# Speisung.net
KiCad netlist of a schematic drawn in Altium Designer
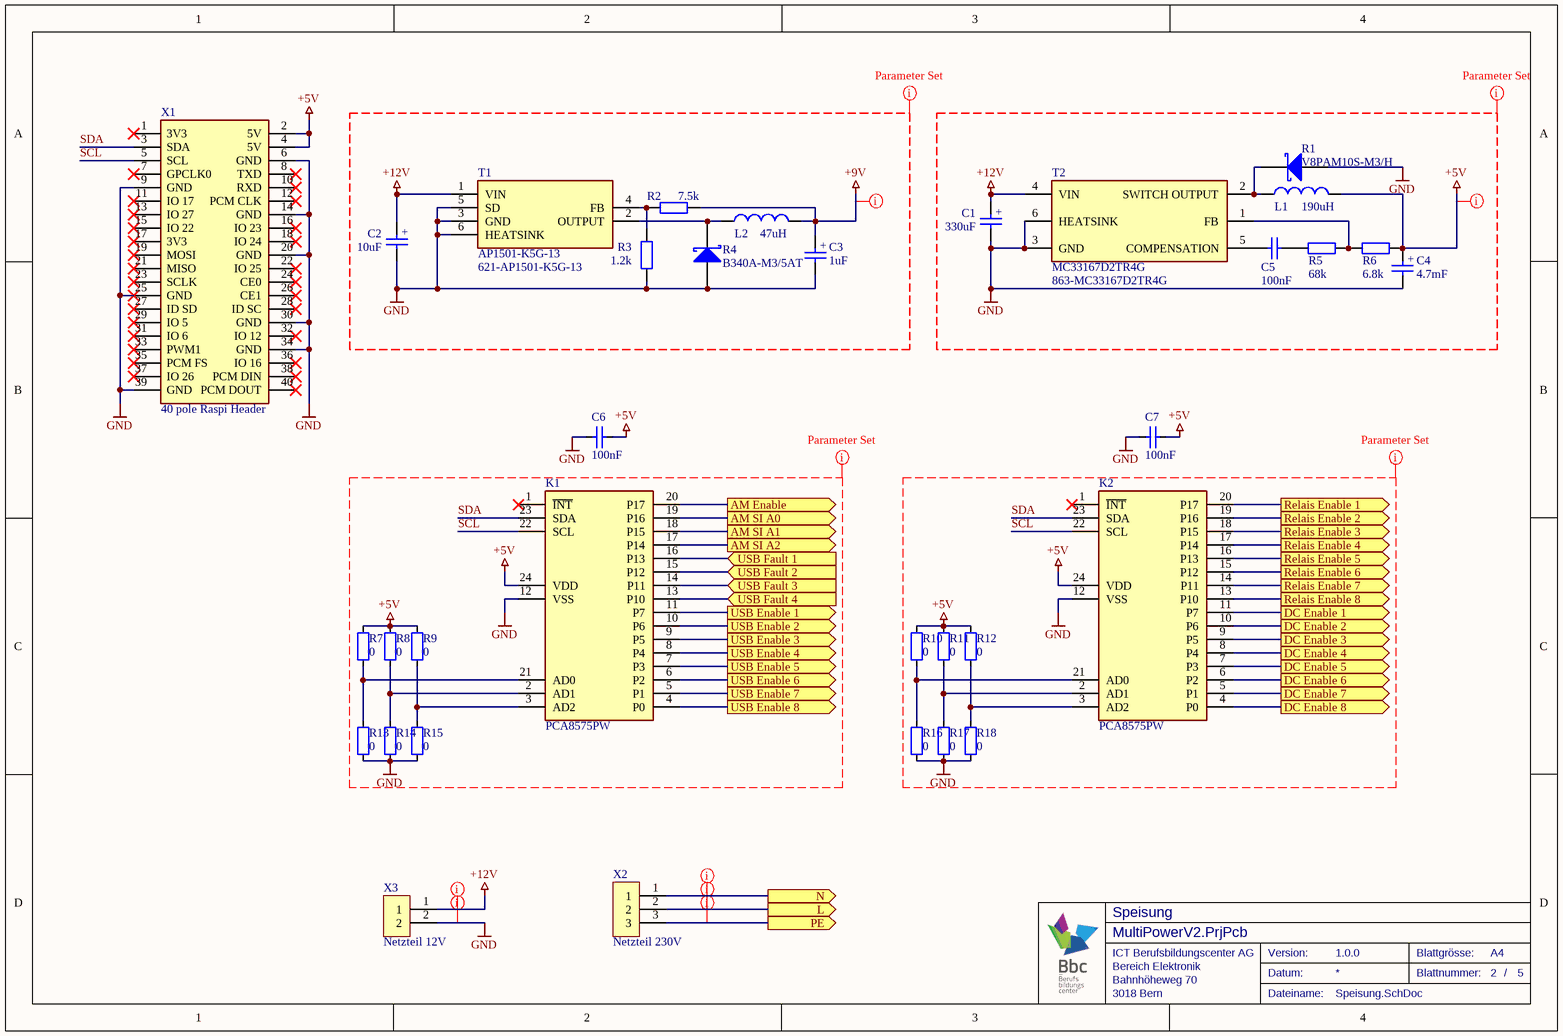
[diagram p0: Speisung.SchDoc]

(export (version "E")
  (design (tool "Eeschema 10.0.6"))
  (components
    (comp (ref "C1")
      (value "330uF")
      (footprint "T521X337M016ATE015")
      (description "Polarized Capacitor")
      (fields (field (name "Comment") "Capacitor") (field (name "PUBLISHER") "ICT Berufsbildungscenter AG"))
      (libsource (lib "BBC_Components") (part "Capacitor P"))
    )
    (comp (ref "C2")
      (value "10uF")
      (footprint "CAP TAN A R")
      (description "Polarized Capacitor")
      (fields (field (name "Comment") "Capacitor") (field (name "PUBLISHER") "ICT Berufsbildungscenter AG"))
      (libsource (lib "BBC_Components") (part "Capacitor P"))
    )
    (comp (ref "C3")
      (value "1uF")
      (footprint "R82EC4100Z370J")
      (description "Polarized Capacitor")
      (fields (field (name "Comment") "Capacitor") (field (name "PUBLISHER") "ICT Berufsbildungscenter AG"))
      (libsource (lib "BBC_Components") (part "Capacitor P"))
    )
    (comp (ref "C4")
      (value "4.7mF")
      (footprint "CAP ELKO 12.5x20x5 S")
      (description "Polarized Capacitor")
      (fields (field (name "Comment") "Capacitor") (field (name "PUBLISHER") "ICT Berufsbildungscenter AG"))
      (libsource (lib "BBC_Components") (part "Capacitor P"))
    )
    (comp (ref "C5")
      (value "100nF")
      (footprint "CAP CER 1206 H")
      (description "Non polarized capacitor")
      (fields (field (name "Comment") "Capacitor") (field (name "PUBLISHER") "ICT Berufsbildungscenter AG"))
      (libsource (lib "BBC_Components") (part "Capacitor"))
    )
    (comp (ref "C6")
      (value "100nF")
      (footprint "CAP CER 0805 R")
      (description "Non polarized capacitor")
      (fields (field (name "Comment") "Capacitor") (field (name "PUBLISHER") "ICT Berufsbildungscenter AG"))
      (libsource (lib "SchematicLibrary") (part "Capacitor"))
    )
    (comp (ref "C7")
      (value "100nF")
      (footprint "CAP CER 0805 R")
      (description "Non polarized capacitor")
      (fields (field (name "Comment") "Capacitor") (field (name "PUBLISHER") "ICT Berufsbildungscenter AG"))
      (libsource (lib "SchematicLibrary") (part "Capacitor"))
    )
    (comp (ref "K1")
      (value "PCA8575PW")
      (footprint "TSOP65P640X110-24M")
      (libsource (lib "SchematicLibrary") (part "PCA8575PW"))
    )
    (comp (ref "K2")
      (value "PCA8575PW")
      (footprint "TSOP65P640X110-24M")
      (libsource (lib "SchematicLibrary") (part "PCA8575PW"))
    )
    (comp (ref "L1")
      (value "190uH")
      (footprint "SHBC14-1R2A0187V")
      (description "Inductor")
      (fields (field (name "PUBLISHER") "ICT Berufsbildungscenter AG"))
      (libsource (lib "BBC_Components") (part "Inductor"))
    )
    (comp (ref "L2")
      (value "47uH")
      (footprint "SRP1038C6R8M")
      (description "Inductor")
      (fields (field (name "PUBLISHER") "ICT Berufsbildungscenter AG"))
      (libsource (lib "BBC_Components") (part "Inductor"))
    )
    (comp (ref "R1")
      (value "V8PAM10S-M3/H")
      (footprint "DO-221BC")
      (description "Schottky Diode")
      (fields (field (name "PUBLISHER") "ICT Berufsbildungscenter AG"))
      (libsource (lib "BBC_Components") (part "Schottky Diode"))
    )
    (comp (ref "R2")
      (value "7.5k")
      (footprint "RESMELF3514N")
      (description "Resistor")
      (fields (field (name "PUBLISHER") "ICT Berufsbildungscenter AG"))
      (libsource (lib "BBC_Components") (part "Resistor"))
    )
    (comp (ref "R3")
      (value "1.2k")
      (footprint "RESMELF3514N")
      (description "Resistor")
      (fields (field (name "PUBLISHER") "ICT Berufsbildungscenter AG"))
      (libsource (lib "") (part "Resistor_1"))
    )
    (comp (ref "R4")
      (value "B340A-M3/5AT")
      (footprint "DO-214AC")
      (description "Schottky Diode")
      (fields (field (name "PUBLISHER") "ICT Berufsbildungscenter AG"))
      (libsource (lib "BBC_Components") (part "Schottky Diode"))
    )
    (comp (ref "R5")
      (value "68k")
      (footprint "RESMELF3514N")
      (description "Resistor")
      (fields (field (name "PUBLISHER") "ICT Berufsbildungscenter AG"))
      (libsource (lib "BBC_Components") (part "Resistor"))
    )
    (comp (ref "R6")
      (value "6.8k")
      (footprint "RESMELF3514N")
      (description "Resistor")
      (fields (field (name "PUBLISHER") "ICT Berufsbildungscenter AG"))
      (libsource (lib "BBC_Components") (part "Resistor"))
    )
    (comp (ref "R7")
      (value "0")
      (footprint "RES 1206 H")
      (description "Resistor")
      (fields (field (name "PUBLISHER") "ICT Berufsbildungscenter AG"))
      (libsource (lib "SchematicLibrary") (part "Resistor"))
    )
    (comp (ref "R8")
      (value "0")
      (footprint "RES 1206 H")
      (description "Resistor")
      (fields (field (name "PUBLISHER") "ICT Berufsbildungscenter AG"))
      (libsource (lib "SchematicLibrary") (part "Resistor"))
    )
    (comp (ref "R9")
      (value "0")
      (footprint "RES 1206 H")
      (description "Resistor")
      (fields (field (name "PUBLISHER") "ICT Berufsbildungscenter AG"))
      (libsource (lib "SchematicLibrary") (part "Resistor"))
    )
    (comp (ref "R10")
      (value "0")
      (footprint "RES 1206 H")
      (description "Resistor")
      (fields (field (name "PUBLISHER") "ICT Berufsbildungscenter AG"))
      (libsource (lib "SchematicLibrary") (part "Resistor"))
    )
    (comp (ref "R11")
      (value "0")
      (footprint "RES 1206 H")
      (description "Resistor")
      (fields (field (name "PUBLISHER") "ICT Berufsbildungscenter AG"))
      (libsource (lib "SchematicLibrary") (part "Resistor"))
    )
    (comp (ref "R12")
      (value "0")
      (footprint "RES 1206 H")
      (description "Resistor")
      (fields (field (name "PUBLISHER") "ICT Berufsbildungscenter AG"))
      (libsource (lib "SchematicLibrary") (part "Resistor"))
    )
    (comp (ref "R13")
      (value "0")
      (footprint "RES 1206 H")
      (description "Resistor")
      (fields (field (name "PUBLISHER") "ICT Berufsbildungscenter AG"))
      (libsource (lib "SchematicLibrary") (part "Resistor"))
    )
    (comp (ref "R14")
      (value "0")
      (footprint "RES 1206 H")
      (description "Resistor")
      (fields (field (name "PUBLISHER") "ICT Berufsbildungscenter AG"))
      (libsource (lib "SchematicLibrary") (part "Resistor"))
    )
    (comp (ref "R15")
      (value "0")
      (footprint "RES 1206 H")
      (description "Resistor")
      (fields (field (name "PUBLISHER") "ICT Berufsbildungscenter AG"))
      (libsource (lib "SchematicLibrary") (part "Resistor"))
    )
    (comp (ref "R16")
      (value "0")
      (footprint "RES 1206 H")
      (description "Resistor")
      (fields (field (name "PUBLISHER") "ICT Berufsbildungscenter AG"))
      (libsource (lib "SchematicLibrary") (part "Resistor"))
    )
    (comp (ref "R17")
      (value "0")
      (footprint "RES 1206 H")
      (description "Resistor")
      (fields (field (name "PUBLISHER") "ICT Berufsbildungscenter AG"))
      (libsource (lib "SchematicLibrary") (part "Resistor"))
    )
    (comp (ref "R18")
      (value "0")
      (footprint "RES 1206 H")
      (description "Resistor")
      (fields (field (name "PUBLISHER") "ICT Berufsbildungscenter AG"))
      (libsource (lib "SchematicLibrary") (part "Resistor"))
    )
    (comp (ref "T1")
      (value "AP1501-K5G-13")
      (footprint "TO-263-5L")
      (description "Switching Voltage Regulators")
      (fields (field (name "SUPPLIER PART NUMBER 1") "621-AP1501-K5G-13"))
      (libsource (lib "SchematicLibrary") (part "AP1501-K5G-13"))
    )
    (comp (ref "T2")
      (value "MC33167D2TR4G")
      (footprint "TO-263-5")
      (description "Switching Voltage Regulators")
      (fields
        (field (name "MOUSER PART NUMBER") "863-MC33167D2TR4G")
        (field (name "SUPPLIER PART NUMBER 1") "863-MC33167D2TR4G")
      )
      (libsource (lib "SchematicLibrary") (part "MC33167D2TR4G"))
    )
    (comp (ref "X1")
      (value "40 pole Raspi Header")
      (footprint "Header SMD Male 2x20 H")
      (description "board to board header")
      (fields (field (name "PUBLISHER") "ICT Berufsbildungscenter AG"))
      (libsource (lib "SchematicLibrary") (part "RaspberryHeader40"))
    )
    (comp (ref "X2")
      (value "Netzteil 230V")
      (footprint "282841-3")
      (description "board to board header")
      (fields (field (name "PUBLISHER") "ICT Berufsbildungscenter AG"))
      (libsource (lib "BBC_Components") (part "Header 3"))
    )
    (comp (ref "X3")
      (value "Netzteil 12V")
      (footprint "282841-2")
      (description "board to board header")
      (fields (field (name "PUBLISHER") "ICT Berufsbildungscenter AG"))
      (libsource (lib "BBC_Components") (part "Header 2"))
    )
  )
  (nets
    (net (code "1") (name "+5V") (class "Default")
      (node (ref "C4") (pin "A") (pinfunction "Anode_A") (pintype "passive"))
      (node (ref "C6") (pin "2") (pinfunction "2_2") (pintype "passive"))
      (node (ref "C7") (pin "2") (pinfunction "2_2") (pintype "passive"))
      (node (ref "K1") (pin "24") (pinfunction "VDD_24") (pintype "passive"))
      (node (ref "K2") (pin "24") (pinfunction "VDD_24") (pintype "passive"))
      (node (ref "L1") (pin "2") (pinfunction "2_2") (pintype "passive"))
      (node (ref "R10") (pin "2") (pinfunction "2_2") (pintype "passive"))
      (node (ref "R11") (pin "2") (pinfunction "2_2") (pintype "passive"))
      (node (ref "R12") (pin "2") (pinfunction "2_2") (pintype "passive"))
      (node (ref "R6") (pin "2") (pinfunction "2_2") (pintype "passive"))
      (node (ref "R7") (pin "2") (pinfunction "2_2") (pintype "passive"))
      (node (ref "R8") (pin "2") (pinfunction "2_2") (pintype "passive"))
      (node (ref "R9") (pin "2") (pinfunction "2_2") (pintype "passive"))
      (node (ref "X1") (pin "2") (pinfunction "5V_2") (pintype "passive"))
      (node (ref "X1") (pin "4") (pinfunction "5V_4") (pintype "passive"))
    )
    (net (code "2") (name "+9V") (class "Default")
      (node (ref "C3") (pin "A") (pinfunction "Anode_A") (pintype "passive"))
      (node (ref "L2") (pin "2") (pinfunction "2_2") (pintype "passive"))
      (node (ref "R2") (pin "2") (pinfunction "2_2") (pintype "passive"))
    )
    (net (code "3") (name "+12V") (class "Default")
      (node (ref "C1") (pin "A") (pinfunction "Anode_A") (pintype "passive"))
      (node (ref "C2") (pin "A") (pinfunction "Anode_A") (pintype "passive"))
      (node (ref "T1") (pin "1") (pinfunction "VIN_1") (pintype "passive"))
      (node (ref "T2") (pin "4") (pinfunction "VIN_4") (pintype "passive"))
      (node (ref "X3") (pin "1") (pinfunction "1_1") (pintype "passive"))
    )
    (net (code "4") (name "/AM Enable") (class "Default")
      (node (ref "K1") (pin "20") (pinfunction "P17_20") (pintype "passive"))
    )
    (net (code "5") (name "/AM SI A0") (class "Default")
      (node (ref "K1") (pin "19") (pinfunction "P16_19") (pintype "passive"))
    )
    (net (code "6") (name "/AM SI A1") (class "Default")
      (node (ref "K1") (pin "18") (pinfunction "P15_18") (pintype "passive"))
    )
    (net (code "7") (name "/AM SI A2") (class "Default")
      (node (ref "K1") (pin "17") (pinfunction "P14_17") (pintype "passive"))
    )
    (net (code "8") (name "/DC Enable 1") (class "Default")
      (node (ref "K2") (pin "11") (pinfunction "P7_11") (pintype "passive"))
    )
    (net (code "9") (name "/DC Enable 2") (class "Default")
      (node (ref "K2") (pin "10") (pinfunction "P6_10") (pintype "passive"))
    )
    (net (code "10") (name "/DC Enable 3") (class "Default")
      (node (ref "K2") (pin "9") (pinfunction "P5_9") (pintype "passive"))
    )
    (net (code "11") (name "/DC Enable 4") (class "Default")
      (node (ref "K2") (pin "8") (pinfunction "P4_8") (pintype "passive"))
    )
    (net (code "12") (name "/DC Enable 5") (class "Default")
      (node (ref "K2") (pin "7") (pinfunction "P3_7") (pintype "passive"))
    )
    (net (code "13") (name "/DC Enable 6") (class "Default")
      (node (ref "K2") (pin "6") (pinfunction "P2_6") (pintype "passive"))
    )
    (net (code "14") (name "/DC Enable 7") (class "Default")
      (node (ref "K2") (pin "5") (pinfunction "P1_5") (pintype "passive"))
    )
    (net (code "15") (name "/DC Enable 8") (class "Default")
      (node (ref "K2") (pin "4") (pinfunction "P0_4") (pintype "passive"))
    )
    (net (code "16") (name "/L") (class "Default")
      (node (ref "X2") (pin "2") (pinfunction "2_2") (pintype "passive"))
    )
    (net (code "17") (name "/N") (class "Default")
      (node (ref "X2") (pin "1") (pinfunction "1_1") (pintype "passive"))
    )
    (net (code "18") (name "/PE") (class "Default")
      (node (ref "X2") (pin "3") (pinfunction "3_3") (pintype "passive"))
    )
    (net (code "19") (name "/Relais Enable 1") (class "Default")
      (node (ref "K2") (pin "20") (pinfunction "P17_20") (pintype "passive"))
    )
    (net (code "20") (name "/Relais Enable 2") (class "Default")
      (node (ref "K2") (pin "19") (pinfunction "P16_19") (pintype "passive"))
    )
    (net (code "21") (name "/Relais Enable 3") (class "Default")
      (node (ref "K2") (pin "18") (pinfunction "P15_18") (pintype "passive"))
    )
    (net (code "22") (name "/Relais Enable 4") (class "Default")
      (node (ref "K2") (pin "17") (pinfunction "P14_17") (pintype "passive"))
    )
    (net (code "23") (name "/Relais Enable 5") (class "Default")
      (node (ref "K2") (pin "16") (pinfunction "P13_16") (pintype "passive"))
    )
    (net (code "24") (name "/Relais Enable 6") (class "Default")
      (node (ref "K2") (pin "15") (pinfunction "P12_15") (pintype "passive"))
    )
    (net (code "25") (name "/Relais Enable 7") (class "Default")
      (node (ref "K2") (pin "14") (pinfunction "P11_14") (pintype "passive"))
    )
    (net (code "26") (name "/Relais Enable 8") (class "Default")
      (node (ref "K2") (pin "13") (pinfunction "P10_13") (pintype "passive"))
    )
    (net (code "27") (name "/SCL") (class "Default")
      (node (ref "K1") (pin "22") (pinfunction "SCL_22") (pintype "passive"))
      (node (ref "K2") (pin "22") (pinfunction "SCL_22") (pintype "passive"))
      (node (ref "X1") (pin "5") (pinfunction "SCL_5") (pintype "passive"))
    )
    (net (code "28") (name "/SDA") (class "Default")
      (node (ref "K1") (pin "23") (pinfunction "SDA_23") (pintype "passive"))
      (node (ref "K2") (pin "23") (pinfunction "SDA_23") (pintype "passive"))
      (node (ref "X1") (pin "3") (pinfunction "SDA_3") (pintype "passive"))
    )
    (net (code "29") (name "/USB Enable 1") (class "Default")
      (node (ref "K1") (pin "11") (pinfunction "P7_11") (pintype "passive"))
    )
    (net (code "30") (name "/USB Enable 2") (class "Default")
      (node (ref "K1") (pin "10") (pinfunction "P6_10") (pintype "passive"))
    )
    (net (code "31") (name "/USB Enable 3") (class "Default")
      (node (ref "K1") (pin "9") (pinfunction "P5_9") (pintype "passive"))
    )
    (net (code "32") (name "/USB Enable 4") (class "Default")
      (node (ref "K1") (pin "8") (pinfunction "P4_8") (pintype "passive"))
    )
    (net (code "33") (name "/USB Enable 5") (class "Default")
      (node (ref "K1") (pin "7") (pinfunction "P3_7") (pintype "passive"))
    )
    (net (code "34") (name "/USB Enable 6") (class "Default")
      (node (ref "K1") (pin "6") (pinfunction "P2_6") (pintype "passive"))
    )
    (net (code "35") (name "/USB Enable 7") (class "Default")
      (node (ref "K1") (pin "5") (pinfunction "P1_5") (pintype "passive"))
    )
    (net (code "36") (name "/USB Enable 8") (class "Default")
      (node (ref "K1") (pin "4") (pinfunction "P0_4") (pintype "passive"))
    )
    (net (code "37") (name "/USB Fault 1") (class "Default")
      (node (ref "K1") (pin "16") (pinfunction "P13_16") (pintype "passive"))
    )
    (net (code "38") (name "/USB Fault 2") (class "Default")
      (node (ref "K1") (pin "15") (pinfunction "P12_15") (pintype "passive"))
    )
    (net (code "39") (name "/USB Fault 3") (class "Default")
      (node (ref "K1") (pin "14") (pinfunction "P11_14") (pintype "passive"))
    )
    (net (code "40") (name "/USB Fault 4") (class "Default")
      (node (ref "K1") (pin "13") (pinfunction "P10_13") (pintype "passive"))
    )
    (net (code "41") (name "GND") (class "Default")
      (node (ref "C1") (pin "C") (pinfunction "Cathode_C") (pintype "passive"))
      (node (ref "C2") (pin "C") (pinfunction "Cathode_C") (pintype "passive"))
      (node (ref "C3") (pin "C") (pinfunction "Cathode_C") (pintype "passive"))
      (node (ref "C4") (pin "C") (pinfunction "Cathode_C") (pintype "passive"))
      (node (ref "C6") (pin "1") (pinfunction "1_1") (pintype "passive"))
      (node (ref "C7") (pin "1") (pinfunction "1_1") (pintype "passive"))
      (node (ref "K1") (pin "12") (pinfunction "VSS_12") (pintype "passive"))
      (node (ref "K2") (pin "12") (pinfunction "VSS_12") (pintype "passive"))
      (node (ref "R1") (pin "A") (pinfunction "Anode_A") (pintype "passive"))
      (node (ref "R13") (pin "1") (pinfunction "1_1") (pintype "passive"))
      (node (ref "R14") (pin "1") (pinfunction "1_1") (pintype "passive"))
      (node (ref "R15") (pin "1") (pinfunction "1_1") (pintype "passive"))
      (node (ref "R16") (pin "1") (pinfunction "1_1") (pintype "passive"))
      (node (ref "R17") (pin "1") (pinfunction "1_1") (pintype "passive"))
      (node (ref "R18") (pin "1") (pinfunction "1_1") (pintype "passive"))
      (node (ref "R3") (pin "1") (pinfunction "1_1") (pintype "passive"))
      (node (ref "R4") (pin "A") (pinfunction "Anode_A") (pintype "passive"))
      (node (ref "T1") (pin "3") (pinfunction "GND_3") (pintype "passive"))
      (node (ref "T1") (pin "5") (pinfunction "SD_5") (pintype "passive"))
      (node (ref "T1") (pin "6") (pinfunction "HEATSINK_6") (pintype "passive"))
      (node (ref "T2") (pin "3") (pinfunction "GND_3") (pintype "passive"))
      (node (ref "T2") (pin "6") (pinfunction "HEATSINK_6") (pintype "passive"))
      (node (ref "X1") (pin "14") (pinfunction "GND_14") (pintype "passive"))
      (node (ref "X1") (pin "20") (pinfunction "GND_20") (pintype "passive"))
      (node (ref "X1") (pin "25") (pinfunction "GND_25") (pintype "passive"))
      (node (ref "X1") (pin "30") (pinfunction "GND_30") (pintype "passive"))
      (node (ref "X1") (pin "34") (pinfunction "GND_34") (pintype "passive"))
      (node (ref "X1") (pin "39") (pinfunction "GND_39") (pintype "passive"))
      (node (ref "X1") (pin "6") (pinfunction "GND_6") (pintype "passive"))
      (node (ref "X1") (pin "9") (pinfunction "GND_9") (pintype "passive"))
      (node (ref "X3") (pin "2") (pinfunction "2_2") (pintype "passive"))
    )
    (net (code "42") (name "Net-(C5-Pad1)") (class "Default")
      (node (ref "C5") (pin "1") (pinfunction "1_1") (pintype "passive"))
      (node (ref "R5") (pin "1") (pinfunction "1_1") (pintype "passive"))
    )
    (net (code "43") (name "Net-(K1-AD0)") (class "Default")
      (node (ref "K1") (pin "21") (pinfunction "AD0_21") (pintype "passive"))
      (node (ref "R13") (pin "2") (pinfunction "2_2") (pintype "passive"))
      (node (ref "R7") (pin "1") (pinfunction "1_1") (pintype "passive"))
    )
    (net (code "44") (name "Net-(K1-AD1)") (class "Default")
      (node (ref "K1") (pin "2") (pinfunction "AD1_2") (pintype "passive"))
      (node (ref "R14") (pin "2") (pinfunction "2_2") (pintype "passive"))
      (node (ref "R8") (pin "1") (pinfunction "1_1") (pintype "passive"))
    )
    (net (code "45") (name "Net-(K1-AD2)") (class "Default")
      (node (ref "K1") (pin "3") (pinfunction "AD2_3") (pintype "passive"))
      (node (ref "R15") (pin "2") (pinfunction "2_2") (pintype "passive"))
      (node (ref "R9") (pin "1") (pinfunction "1_1") (pintype "passive"))
    )
    (net (code "46") (name "Net-(K2-AD0)") (class "Default")
      (node (ref "K2") (pin "21") (pinfunction "AD0_21") (pintype "passive"))
      (node (ref "R10") (pin "1") (pinfunction "1_1") (pintype "passive"))
      (node (ref "R16") (pin "2") (pinfunction "2_2") (pintype "passive"))
    )
    (net (code "47") (name "Net-(K2-AD1)") (class "Default")
      (node (ref "K2") (pin "2") (pinfunction "AD1_2") (pintype "passive"))
      (node (ref "R11") (pin "1") (pinfunction "1_1") (pintype "passive"))
      (node (ref "R17") (pin "2") (pinfunction "2_2") (pintype "passive"))
    )
    (net (code "48") (name "Net-(K2-AD2)") (class "Default")
      (node (ref "K2") (pin "3") (pinfunction "AD2_3") (pintype "passive"))
      (node (ref "R12") (pin "1") (pinfunction "1_1") (pintype "passive"))
      (node (ref "R18") (pin "2") (pinfunction "2_2") (pintype "passive"))
    )
    (net (code "49") (name "Net-(R1-Cathode)") (class "Default")
      (node (ref "L1") (pin "1") (pinfunction "1_1") (pintype "passive"))
      (node (ref "R1") (pin "C") (pinfunction "Cathode_C") (pintype "passive"))
      (node (ref "T2") (pin "2") (pinfunction "SWITCH_OUTPUT_2") (pintype "passive"))
    )
    (net (code "50") (name "Net-(R4-Cathode)") (class "Default")
      (node (ref "L2") (pin "1") (pinfunction "1_1") (pintype "passive"))
      (node (ref "R4") (pin "C") (pinfunction "Cathode_C") (pintype "passive"))
      (node (ref "T1") (pin "2") (pinfunction "OUTPUT_2") (pintype "passive"))
    )
    (net (code "51") (name "Net-(T1-FB)") (class "Default")
      (node (ref "R2") (pin "1") (pinfunction "1_1") (pintype "passive"))
      (node (ref "R3") (pin "2") (pinfunction "2_2") (pintype "passive"))
      (node (ref "T1") (pin "4") (pinfunction "FB_4") (pintype "passive"))
    )
    (net (code "52") (name "Net-(T2-COMPENSATION)") (class "Default")
      (node (ref "C5") (pin "2") (pinfunction "2_2") (pintype "passive"))
      (node (ref "T2") (pin "5") (pinfunction "COMPENSATION_5") (pintype "passive"))
    )
    (net (code "53") (name "Net-(T2-FB)") (class "Default")
      (node (ref "R5") (pin "2") (pinfunction "2_2") (pintype "passive"))
      (node (ref "R6") (pin "1") (pinfunction "1_1") (pintype "passive"))
      (node (ref "T2") (pin "1") (pinfunction "FB_1") (pintype "passive"))
    )
    (net (code "54") (name "unconnected-(K1-~{INT}-Pad1)") (class "Default")
      (node (ref "K1") (pin "1") (pinfunction "~{INT}_1") (pintype "passive+no_connect"))
    )
    (net (code "55") (name "unconnected-(K2-~{INT}-Pad1)") (class "Default")
      (node (ref "K2") (pin "1") (pinfunction "~{INT}_1") (pintype "passive+no_connect"))
    )
    (net (code "56") (name "unconnected-(X1-3V3-Pad1)") (class "Default")
      (node (ref "X1") (pin "1") (pinfunction "3V3_1") (pintype "passive+no_connect"))
    )
    (net (code "57") (name "unconnected-(X1-3V3-Pad17)") (class "Default")
      (node (ref "X1") (pin "17") (pinfunction "3V3_17") (pintype "passive+no_connect"))
    )
    (net (code "58") (name "unconnected-(X1-CE0-Pad24)") (class "Default")
      (node (ref "X1") (pin "24") (pinfunction "CE0_24") (pintype "passive+no_connect"))
    )
    (net (code "59") (name "unconnected-(X1-CE1-Pad26)") (class "Default")
      (node (ref "X1") (pin "26") (pinfunction "CE1_26") (pintype "passive+no_connect"))
    )
    (net (code "60") (name "unconnected-(X1-GPCLK0-Pad7)") (class "Default")
      (node (ref "X1") (pin "7") (pinfunction "GPCLK0_7") (pintype "passive+no_connect"))
    )
    (net (code "61") (name "unconnected-(X1-ID_SC-Pad28)") (class "Default")
      (node (ref "X1") (pin "28") (pinfunction "ID_SC_28") (pintype "passive+no_connect"))
    )
    (net (code "62") (name "unconnected-(X1-ID_SD-Pad27)") (class "Default")
      (node (ref "X1") (pin "27") (pinfunction "ID_SD_27") (pintype "passive+no_connect"))
    )
    (net (code "63") (name "unconnected-(X1-IO_5-Pad29)") (class "Default")
      (node (ref "X1") (pin "29") (pinfunction "IO_5_29") (pintype "passive+no_connect"))
    )
    (net (code "64") (name "unconnected-(X1-IO_6-Pad31)") (class "Default")
      (node (ref "X1") (pin "31") (pinfunction "IO_6_31") (pintype "passive+no_connect"))
    )
    (net (code "65") (name "unconnected-(X1-IO_12-Pad32)") (class "Default")
      (node (ref "X1") (pin "32") (pinfunction "IO_12_32") (pintype "passive+no_connect"))
    )
    (net (code "66") (name "unconnected-(X1-IO_16-Pad36)") (class "Default")
      (node (ref "X1") (pin "36") (pinfunction "IO_16_36") (pintype "passive+no_connect"))
    )
    (net (code "67") (name "unconnected-(X1-IO_17-Pad11)") (class "Default")
      (node (ref "X1") (pin "11") (pinfunction "IO_17_11") (pintype "passive+no_connect"))
    )
    (net (code "68") (name "unconnected-(X1-IO_22-Pad15)") (class "Default")
      (node (ref "X1") (pin "15") (pinfunction "IO_22_15") (pintype "passive+no_connect"))
    )
    (net (code "69") (name "unconnected-(X1-IO_23-Pad16)") (class "Default")
      (node (ref "X1") (pin "16") (pinfunction "IO_23_16") (pintype "passive+no_connect"))
    )
    (net (code "70") (name "unconnected-(X1-IO_24-Pad18)") (class "Default")
      (node (ref "X1") (pin "18") (pinfunction "IO_24_18") (pintype "passive+no_connect"))
    )
    (net (code "71") (name "unconnected-(X1-IO_25-Pad22)") (class "Default")
      (node (ref "X1") (pin "22") (pinfunction "IO_25_22") (pintype "passive+no_connect"))
    )
    (net (code "72") (name "unconnected-(X1-IO_26-Pad37)") (class "Default")
      (node (ref "X1") (pin "37") (pinfunction "IO_26_37") (pintype "passive+no_connect"))
    )
    (net (code "73") (name "unconnected-(X1-IO_27-Pad13)") (class "Default")
      (node (ref "X1") (pin "13") (pinfunction "IO_27_13") (pintype "passive+no_connect"))
    )
    (net (code "74") (name "unconnected-(X1-MISO-Pad21)") (class "Default")
      (node (ref "X1") (pin "21") (pinfunction "MISO_21") (pintype "passive+no_connect"))
    )
    (net (code "75") (name "unconnected-(X1-MOSI-Pad19)") (class "Default")
      (node (ref "X1") (pin "19") (pinfunction "MOSI_19") (pintype "passive+no_connect"))
    )
    (net (code "76") (name "unconnected-(X1-PCM_CLK-Pad12)") (class "Default")
      (node (ref "X1") (pin "12") (pinfunction "PCM_CLK_12") (pintype "passive+no_connect"))
    )
    (net (code "77") (name "unconnected-(X1-PCM_DIN-Pad38)") (class "Default")
      (node (ref "X1") (pin "38") (pinfunction "PCM_DIN_38") (pintype "passive+no_connect"))
    )
    (net (code "78") (name "unconnected-(X1-PCM_DOUT-Pad40)") (class "Default")
      (node (ref "X1") (pin "40") (pinfunction "PCM_DOUT_40") (pintype "passive+no_connect"))
    )
    (net (code "79") (name "unconnected-(X1-PCM_FS-Pad35)") (class "Default")
      (node (ref "X1") (pin "35") (pinfunction "PCM_FS_35") (pintype "passive+no_connect"))
    )
    (net (code "80") (name "unconnected-(X1-PWM1-Pad33)") (class "Default")
      (node (ref "X1") (pin "33") (pinfunction "PWM1_33") (pintype "passive+no_connect"))
    )
    (net (code "81") (name "unconnected-(X1-RXD-Pad10)") (class "Default")
      (node (ref "X1") (pin "10") (pinfunction "RXD_10") (pintype "passive+no_connect"))
    )
    (net (code "82") (name "unconnected-(X1-SCLK-Pad23)") (class "Default")
      (node (ref "X1") (pin "23") (pinfunction "SCLK_23") (pintype "passive+no_connect"))
    )
    (net (code "83") (name "unconnected-(X1-TXD-Pad8)") (class "Default")
      (node (ref "X1") (pin "8") (pinfunction "TXD_8") (pintype "passive+no_connect"))
    )
  )
)
